# USB.net
KiCad netlist of a schematic drawn in Altium Designer
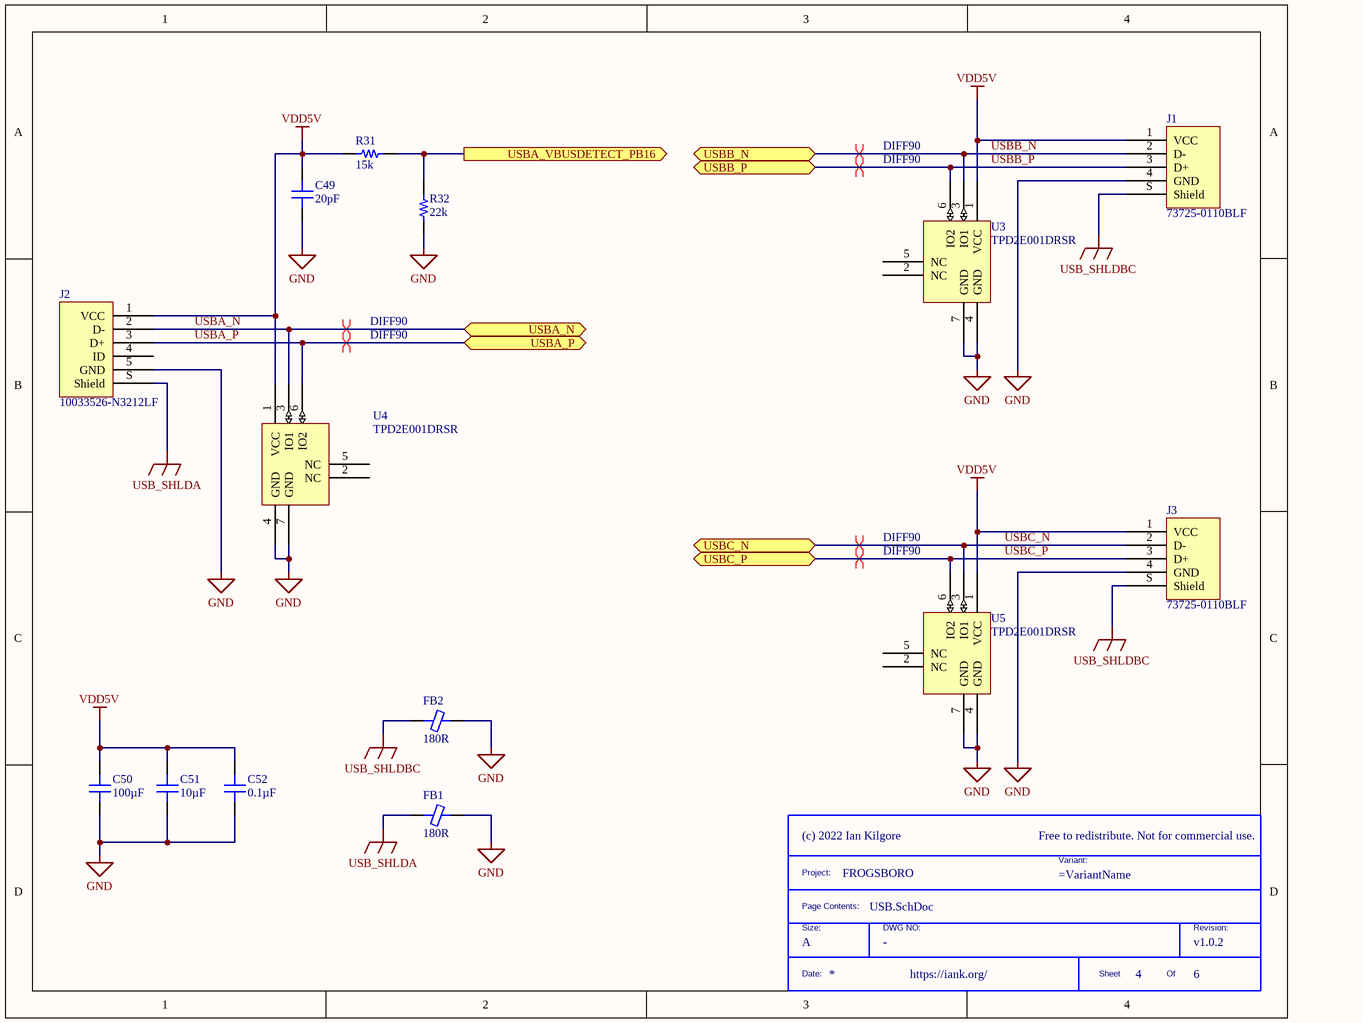
[diagram p0: USB.SchDoc]

(export (version "E")
  (design (tool "Eeschema 10.0.6"))
  (components
    (comp (ref "C49")
      (value "20pF")
      (footprint "CAP 0402_1005")
      (description "CAP CER 20PF 50V C0G/NP0 0402")
      (fields
        (field (name "PART NUMBER") "GJM1555C1H200FB01D")
        (field (name "MANUFACTURER") "Murata Electronics")
      )
      (libsource (lib "Celestial Altium Library - altium_library") (part "Capacitor"))
    )
    (comp (ref "C50")
      (value "100µF")
      (footprint "CAP 1210_3225 - 2.8MM")
      (description "CAP CER 100UF 10V X5R 1210")
      (fields (field (name "PART NUMBER") "LMK325ABJ107MMHP") (field (name "MANUFACTURER") "Taiyo Yuden"))
      (libsource (lib "Celestial Altium Library - altium_library") (part "Capacitor"))
    )
    (comp (ref "C51")
      (value "10µF")
      (footprint "CAP 0805_2012")
      (description "CAP CER 10UF 10V X5R 0805")
      (fields
        (field (name "PART NUMBER") "CL21A106KPCLQNC")
        (field (name "MANUFACTURER") "Samsung Electro-Mechanics")
      )
      (libsource (lib "Celestial Altium Library - altium_library") (part "Capacitor"))
    )
    (comp (ref "C52")
      (value "0.1µF")
      (footprint "CAP 0402_1005")
      (description "CAP CER 0.1UF 16V X5R 0402")
      (fields (field (name "PART NUMBER") "C0402C104K4PACTU") (field (name "MANUFACTURER") "KEMET"))
      (libsource (lib "Celestial Altium Library - altium_library") (part "Capacitor"))
    )
    (comp (ref "FB1")
      (value "180R")
      (footprint "FER 0603_1608")
      (description "FERRITE BEAD 180 OHM 0603 1LN")
      (fields (field (name "PART NUMBER") "MPZ1608S181ATAH0") (field (name "MANUFACTURER") "TDK Corporation"))
      (libsource (lib "Celestial Altium Library - altium_library") (part "Ferrite Chip"))
    )
    (comp (ref "FB2")
      (value "180R")
      (footprint "FER 0603_1608")
      (description "FERRITE BEAD 180 OHM 0603 1LN")
      (fields (field (name "PART NUMBER") "MPZ1608S181ATAH0") (field (name "MANUFACTURER") "TDK Corporation"))
      (libsource (lib "Celestial Altium Library - altium_library") (part "Ferrite Chip"))
    )
    (comp (ref "J1")
      (value "73725-0110BLF")
      (footprint "AMPHENOL USB 73725-0110BLF")
      (description "CONN RCPT USB2.0 TYPEA 4POS R/A")
      (fields (field (name "MANUFACTURER") "Amphenol ICC (FCI)"))
      (libsource (lib "Celestial Altium Library - altium_library") (part "USB 2.0 TYPE A"))
    )
    (comp (ref "J2")
      (value "10033526-N3212LF")
      (footprint "FCI USB 10033526-N3212LF")
      (description "CONN RCPT MINI USB B 5POS SMD RA")
      (fields (field (name "MANUFACTURER") "Amphenol ICC (FCI)"))
      (libsource (lib "Celestial Altium Library - altium_library") (part "USB 2.0 Type B Micro"))
    )
    (comp (ref "J3")
      (value "73725-0110BLF")
      (footprint "AMPHENOL USB 73725-0110BLF")
      (description "CONN RCPT USB2.0 TYPEA 4POS R/A")
      (fields (field (name "MANUFACTURER") "Amphenol ICC (FCI)"))
      (libsource (lib "Celestial Altium Library - altium_library") (part "USB 2.0 TYPE A"))
    )
    (comp (ref "R31")
      (value "15k")
      (footprint "RES 0402_1005")
      (description "RES SMD 15K OHM 1% 1/5W 0402")
      (fields
        (field (name "PART NUMBER") "ERJ-PA2F1502X")
        (field (name "MANUFACTURER") "Panasonic Electronic Components")
      )
      (libsource (lib "Celestial Altium Library - altium_library") (part "Resistor"))
    )
    (comp (ref "R32")
      (value "22k")
      (footprint "RES 0402_1005")
      (description "RES SMD 22K OHM 1% 1/16W 0402")
      (fields (field (name "PART NUMBER") "CR0402-FX-2202GLF") (field (name "MANUFACTURER") "Bourns Inc."))
      (libsource (lib "Celestial Altium Library - altium_library") (part "Resistor"))
    )
    (comp (ref "U3")
      (value "TPD2E001DRSR")
      (footprint "FROGSBORO:SON95P300X80_HS-7N")
      (fields (field (name "MANUFACTURER") "Texas Instruments"))
      (libsource (lib "FROGSBORO") (part "TPD2E001DRSR"))
    )
    (comp (ref "U4")
      (value "TPD2E001DRSR")
      (footprint "FROGSBORO:SON95P300X80_HS-7N")
      (fields (field (name "MANUFACTURER") "Texas Instruments"))
      (libsource (lib "") (part "TPD2E001DRSR_1"))
    )
    (comp (ref "U5")
      (value "TPD2E001DRSR")
      (footprint "FROGSBORO:SON95P300X80_HS-7N")
      (fields (field (name "MANUFACTURER") "Texas Instruments"))
      (libsource (lib "FROGSBORO") (part "TPD2E001DRSR"))
    )
  )
  (nets
    (net (code "1") (name "/USBA_N") (class "Default")
      (node (ref "J2") (pin "2") (pinfunction "D-_2") (pintype "passive"))
      (node (ref "U4") (pin "3") (pinfunction "IO1_3") (pintype "bidirectional"))
    )
    (net (code "2") (name "/USBA_P") (class "Default")
      (node (ref "J2") (pin "3") (pinfunction "D+_3") (pintype "passive"))
      (node (ref "U4") (pin "6") (pinfunction "IO2_6") (pintype "bidirectional"))
    )
    (net (code "3") (name "/USBA_VBUSDETECT_PB16") (class "Default")
      (node (ref "R31") (pin "2") (pinfunction "2_2") (pintype "passive"))
      (node (ref "R32") (pin "2") (pinfunction "2_2") (pintype "passive"))
    )
    (net (code "4") (name "/USBB_N") (class "Default")
      (node (ref "J1") (pin "2") (pinfunction "D-_2") (pintype "passive"))
      (node (ref "U3") (pin "3") (pinfunction "IO1_3") (pintype "bidirectional"))
    )
    (net (code "5") (name "/USBB_P") (class "Default")
      (node (ref "J1") (pin "3") (pinfunction "D+_3") (pintype "passive"))
      (node (ref "U3") (pin "6") (pinfunction "IO2_6") (pintype "bidirectional"))
    )
    (net (code "6") (name "/USBC_N") (class "Default")
      (node (ref "J3") (pin "2") (pinfunction "D-_2") (pintype "passive"))
      (node (ref "U5") (pin "3") (pinfunction "IO1_3") (pintype "bidirectional"))
    )
    (net (code "7") (name "/USBC_P") (class "Default")
      (node (ref "J3") (pin "3") (pinfunction "D+_3") (pintype "passive"))
      (node (ref "U5") (pin "6") (pinfunction "IO2_6") (pintype "bidirectional"))
    )
    (net (code "8") (name "GND") (class "Default")
      (node (ref "C49") (pin "1") (pinfunction "1_1") (pintype "passive"))
      (node (ref "C50") (pin "1") (pinfunction "1_1") (pintype "passive"))
      (node (ref "C51") (pin "1") (pinfunction "1_1") (pintype "passive"))
      (node (ref "C52") (pin "2") (pinfunction "2_2") (pintype "passive"))
      (node (ref "FB1") (pin "1") (pinfunction "1_1") (pintype "passive"))
      (node (ref "FB2") (pin "1") (pinfunction "1_1") (pintype "passive"))
      (node (ref "J1") (pin "4") (pinfunction "GND_4") (pintype "passive"))
      (node (ref "J2") (pin "5") (pinfunction "GND_5") (pintype "passive"))
      (node (ref "J3") (pin "4") (pinfunction "GND_4") (pintype "passive"))
      (node (ref "R32") (pin "1") (pinfunction "1_1") (pintype "passive"))
      (node (ref "U3") (pin "4") (pinfunction "GND_4") (pintype "power_in"))
      (node (ref "U3") (pin "7") (pinfunction "GND_7") (pintype "power_in"))
      (node (ref "U4") (pin "4") (pinfunction "GND_4") (pintype "power_in"))
      (node (ref "U4") (pin "7") (pinfunction "GND_7") (pintype "power_in"))
      (node (ref "U5") (pin "4") (pinfunction "GND_4") (pintype "power_in"))
      (node (ref "U5") (pin "7") (pinfunction "GND_7") (pintype "power_in"))
    )
    (net (code "9") (name "USB_SHLDA") (class "Default")
      (node (ref "FB1") (pin "2") (pinfunction "2_2") (pintype "passive"))
      (node (ref "J2") (pin "S") (pinfunction "Shield_S") (pintype "passive"))
    )
    (net (code "10") (name "USB_SHLDBC") (class "Default")
      (node (ref "FB2") (pin "2") (pinfunction "2_2") (pintype "passive"))
      (node (ref "J1") (pin "S") (pinfunction "Shield_S") (pintype "passive"))
      (node (ref "J3") (pin "S") (pinfunction "Shield_S") (pintype "passive"))
    )
    (net (code "11") (name "VDD5V") (class "Default")
      (node (ref "C49") (pin "2") (pinfunction "2_2") (pintype "passive"))
      (node (ref "C50") (pin "2") (pinfunction "2_2") (pintype "passive"))
      (node (ref "C51") (pin "2") (pinfunction "2_2") (pintype "passive"))
      (node (ref "C52") (pin "1") (pinfunction "1_1") (pintype "passive"))
      (node (ref "J1") (pin "1") (pinfunction "VCC_1") (pintype "passive"))
      (node (ref "J2") (pin "1") (pinfunction "VCC_1") (pintype "passive"))
      (node (ref "J3") (pin "1") (pinfunction "VCC_1") (pintype "passive"))
      (node (ref "R31") (pin "1") (pinfunction "1_1") (pintype "passive"))
      (node (ref "U3") (pin "1") (pinfunction "VCC_1") (pintype "power_in"))
      (node (ref "U4") (pin "1") (pinfunction "VCC_1") (pintype "power_in"))
      (node (ref "U5") (pin "1") (pinfunction "VCC_1") (pintype "power_in"))
    )
    (net (code "12") (name "unconnected-(J2-ID-Pad4)") (class "Default")
      (node (ref "J2") (pin "4") (pinfunction "ID_4") (pintype "passive"))
    )
    (net (code "13") (name "unconnected-(U3-NC-Pad2)") (class "Default")
      (node (ref "U3") (pin "2") (pinfunction "NC_2") (pintype "passive"))
    )
    (net (code "14") (name "unconnected-(U3-NC-Pad5)") (class "Default")
      (node (ref "U3") (pin "5") (pinfunction "NC_5") (pintype "passive"))
    )
    (net (code "15") (name "unconnected-(U4-NC-Pad2)") (class "Default")
      (node (ref "U4") (pin "2") (pinfunction "NC_2") (pintype "passive"))
    )
    (net (code "16") (name "unconnected-(U4-NC-Pad5)") (class "Default")
      (node (ref "U4") (pin "5") (pinfunction "NC_5") (pintype "passive"))
    )
    (net (code "17") (name "unconnected-(U5-NC-Pad2)") (class "Default")
      (node (ref "U5") (pin "2") (pinfunction "NC_2") (pintype "passive"))
    )
    (net (code "18") (name "unconnected-(U5-NC-Pad5)") (class "Default")
      (node (ref "U5") (pin "5") (pinfunction "NC_5") (pintype "passive"))
    )
  )
)
